# peripherals.net
KiCad netlist of a schematic drawn in Altium Designer
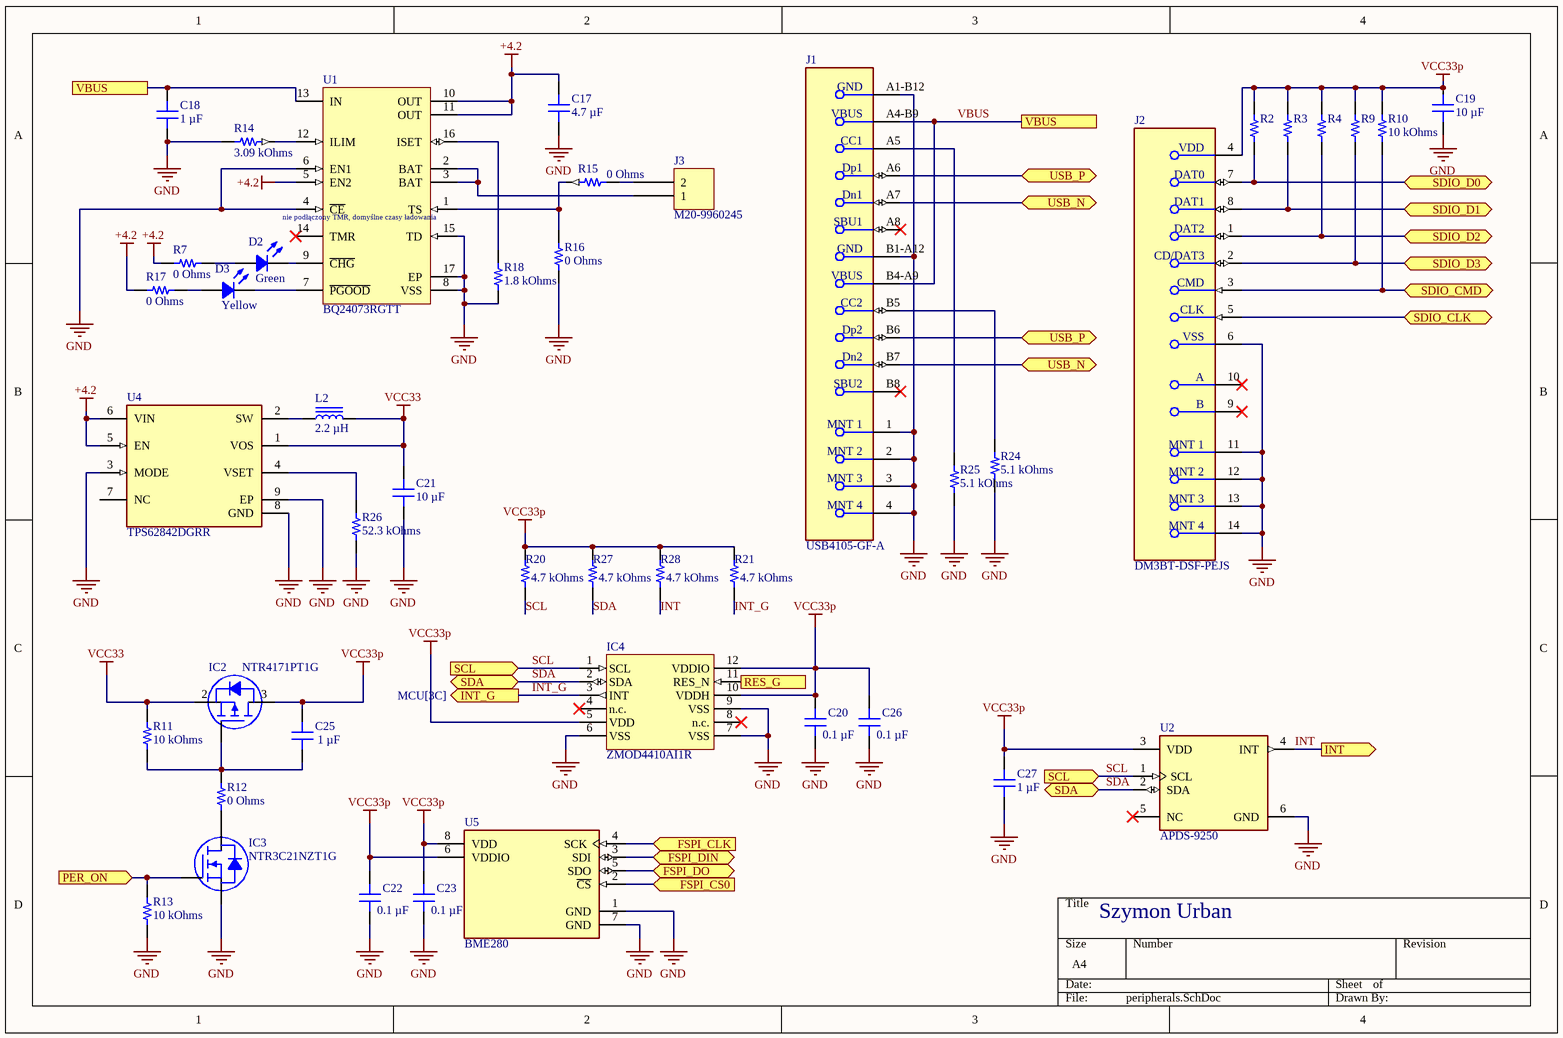
[diagram p0: peripherals.SchDoc]

(export (version "E")
  (design (tool "Eeschema 10.0.6"))
  (components
    (comp (ref "C17")
      (value "4.7 µF")
      (footprint "CAP 0603_1608")
      (description "CAP CER 4.7UF 16V X5R 0603")
      (fields
        (field (name "PART NUMBER") "GRM188R61C475KE11D")
        (field (name "MANUFACTURER") "Murata Electronics")
      )
      (libsource (lib "Celestial Altium Library - altium_library") (part "Capacitor"))
    )
    (comp (ref "C18")
      (value "1 µF")
      (footprint "CAP 0603_1608")
      (description "CAP CER 1UF 10V X7R 0603")
      (fields (field (name "PART NUMBER") "CC0603KRX7R6BB105") (field (name "MANUFACTURER") "Yageo"))
      (libsource (lib "Celestial Altium Library - altium_library") (part "Capacitor"))
    )
    (comp (ref "C19")
      (value "10 µF")
      (footprint "CAP 0603_1608")
      (description "CAP CER 10UF 10V X7T 0603")
      (fields
        (field (name "PART NUMBER") "GRM188D71A106KA73D")
        (field (name "MANUFACTURER") "Murata Electronics")
      )
      (libsource (lib "Celestial Altium Library - altium_library") (part "Capacitor"))
    )
    (comp (ref "C20")
      (value "0.1 µF")
      (footprint "CAP 0603_1608")
      (description "CAP CER 0.1UF 16V X7R 0603")
      (fields (field (name "PART NUMBER") "CS0603KRX7R7BB104") (field (name "MANUFACTURER") "Yageo"))
      (libsource (lib "Celestial Altium Library - altium_library") (part "Capacitor"))
    )
    (comp (ref "C21")
      (value "10 µF")
      (footprint "CAP 0603_1608")
      (description "CAP CER 10UF 10V X7T 0603")
      (fields
        (field (name "PART NUMBER") "GRM188D71A106KA73D")
        (field (name "MANUFACTURER") "Murata Electronics")
      )
      (libsource (lib "Celestial Altium Library - altium_library") (part "Capacitor"))
    )
    (comp (ref "C22")
      (value "0.1 µF")
      (footprint "CAP 0603_1608")
      (description "CAP CER 0.1UF 16V X7R 0603")
      (fields (field (name "PART NUMBER") "CS0603KRX7R7BB104") (field (name "MANUFACTURER") "Yageo"))
      (libsource (lib "Celestial Altium Library - altium_library") (part "Capacitor"))
    )
    (comp (ref "C23")
      (value "0.1 µF")
      (footprint "CAP 0603_1608")
      (description "CAP CER 0.1UF 16V X7R 0603")
      (fields (field (name "PART NUMBER") "CS0603KRX7R7BB104") (field (name "MANUFACTURER") "Yageo"))
      (libsource (lib "Celestial Altium Library - altium_library") (part "Capacitor"))
    )
    (comp (ref "C25")
      (value "1 µF")
      (footprint "CAP 0603_1608")
      (description "CAP CER 1UF 10V X7R 0603")
      (fields
        (field (name "PART NUMBER") "CC0603KRX7R6BB105")
        (field (name "CAPACITANCE") "1 µF")
        (field (name "MANUFACTURER") "Yageo")
      )
      (libsource (lib "Celestial Altium Library - altium_library") (part "Capacitor"))
    )
    (comp (ref "C26")
      (value "0.1 µF")
      (footprint "CAP 0603_1608")
      (description "CAP CER 0.1UF 16V X7R 0603")
      (fields (field (name "PART NUMBER") "CS0603KRX7R7BB104") (field (name "MANUFACTURER") "Yageo"))
      (libsource (lib "Celestial Altium Library - altium_library") (part "Capacitor"))
    )
    (comp (ref "C27")
      (value "1 µF")
      (footprint "CAP 0603_1608")
      (description "CAP CER 1UF 10V X7R 0603")
      (fields (field (name "PART NUMBER") "CC0603KRX7R6BB105") (field (name "MANUFACTURER") "Yageo"))
      (libsource (lib "Celestial Altium Library - altium_library") (part "Capacitor"))
    )
    (comp (ref "D2")
      (value "Green")
      (footprint "LED 0805_2012 GREEN")
      (description "LED GREEN CLEAR 0805 SMD")
      (fields (field (name "PART NUMBER") "150080VS75000") (field (name "MANUFACTURER") "Würth Elektronik"))
      (libsource (lib "Celestial Altium Library - altium_library") (part "LED"))
    )
    (comp (ref "D3")
      (value "Yellow")
      (footprint "LED 0805_2012 YELLOW")
      (description "LED YELLOW CLEAR 0805 SMD")
      (fields (field (name "PART NUMBER") "150080YS75000") (field (name "MANUFACTURER") "Würth Elektronik"))
      (libsource (lib "Celestial Altium Library - altium_library") (part "LED"))
    )
    (comp (ref "IC2")
      (value "NTR4171PT1G")
      (footprint "ON SEMI SOT-23-3")
      (description "MOSFET P-CH 30V 2.2A SOT23")
      (fields (field (name "MANUFACTURER") "ON Semiconductor"))
      (libsource (lib "Celestial Altium Library - altium_library") (part "ON SEMI MOSFET P-CH SOT-23-3"))
    )
    (comp (ref "IC3")
      (value "NTR3C21NZT1G")
      (footprint "ON SEMI SOT-23-3")
      (description "MOSFET N-CH 20V 3.6A SOT23-3")
      (fields (field (name "MANUFACTURER") "ON Semiconductor"))
      (libsource (lib "Celestial Altium Library - altium_library") (part "ON SEMI MOSFET N-CH SOT-23-3"))
    )
    (comp (ref "IC4")
      (value "ZMOD4410AI1R")
      (footprint "ZMODxxxx 12 Leads- LGG12")
      (description "TVOC IAQ INTEGRATED SENSOR")
      (libsource (lib "Altium Content Vault") (part "ZMOD4410AI1R"))
    )
    (comp (ref "J1")
      (value "USB4105-GF-A")
      (footprint "FP-USB4105-GF-A-MFG")
      (description "CONN RCPT USB2.0 TYPEC 5A")
      (fields
        (field (name "MANUFACTURER") "GCT")
        (field (name "OCTOPART") "https://octopart.com/usb4105-gf-a-gct-106627878")
      )
      (libsource (lib "Altium Content Vault") (part "e7c17a616881a82b79941196b4bec10"))
    )
    (comp (ref "J2")
      (value "DM3BT-DSF-PEJS")
      (footprint "FP-DM3BT-DSF-PEJS-MFG")
      (description "CONN MICRO SD CARD PUSH-PUSH R/A")
      (libsource (lib "Altium Content Vault") (part "93546ed2a3e5f67d674769dc1278528"))
    )
    (comp (ref "J3")
      (value "M20-9960245")
      (footprint "HARWIN M20-9960245")
      (description "CONN HEADER R/A 2POS 2.54MM")
      (fields (field (name "MANUFACTURER") "Harwin Inc."))
      (libsource (lib "Celestial Altium Library - altium_library") (part "2 Pin"))
    )
    (comp (ref "L2")
      (value "2.2 µH")
      (footprint "IND 0806_2016")
      (description "FIXED IND 2.2UH 1.8A 116MOHM SMD")
      (fields
        (field (name "PART NUMBER") "DFE201612E-2R2M=P2")
        (field (name "MANUFACTURER") "Murata Electronics")
      )
      (libsource (lib "Celestial Altium Library - altium_library") (part "Inductor"))
    )
    (comp (ref "R2")
      (value "10 kOhms")
      (footprint "RES 0603_1608")
      (description "RES SMD 10K OHM 1% 1/10W 0603")
      (fields (field (name "PART NUMBER") "RT0603FRE0710KL") (field (name "MANUFACTURER") "Yageo"))
      (libsource (lib "Celestial Altium Library - altium_library") (part "Resistor"))
    )
    (comp (ref "R3")
      (value "10 kOhms")
      (footprint "RES 0603_1608")
      (description "RES SMD 10K OHM 1% 1/10W 0603")
      (fields (field (name "PART NUMBER") "RT0603FRE0710KL") (field (name "MANUFACTURER") "Yageo"))
      (libsource (lib "Celestial Altium Library - altium_library") (part "Resistor"))
    )
    (comp (ref "R4")
      (value "10 kOhms")
      (footprint "RES 0603_1608")
      (description "RES SMD 10K OHM 1% 1/10W 0603")
      (fields (field (name "PART NUMBER") "RT0603FRE0710KL") (field (name "MANUFACTURER") "Yageo"))
      (libsource (lib "Celestial Altium Library - altium_library") (part "Resistor"))
    )
    (comp (ref "R7")
      (value "0 Ohms")
      (footprint "RES 0603_1608")
      (description "0603 26 AMP JUMPER")
      (fields (field (name "PART NUMBER") "JR0603X26E") (field (name "MANUFACTURER") "Ohmite"))
      (libsource (lib "Celestial Altium Library - altium_library") (part "Resistor"))
    )
    (comp (ref "R9")
      (value "10 kOhms")
      (footprint "RES 0603_1608")
      (description "RES SMD 10K OHM 1% 1/10W 0603")
      (fields (field (name "PART NUMBER") "RT0603FRE0710KL") (field (name "MANUFACTURER") "Yageo"))
      (libsource (lib "Celestial Altium Library - altium_library") (part "Resistor"))
    )
    (comp (ref "R10")
      (value "10 kOhms")
      (footprint "RES 0603_1608")
      (description "RES SMD 10K OHM 1% 1/10W 0603")
      (fields (field (name "PART NUMBER") "RT0603FRE0710KL") (field (name "MANUFACTURER") "Yageo"))
      (libsource (lib "Celestial Altium Library - altium_library") (part "Resistor"))
    )
    (comp (ref "R11")
      (value "10 kOhms")
      (footprint "RES 0603_1608")
      (description "RES 10K OHM 1% 1/10W 0603")
      (fields (field (name "PART NUMBER") "TNPW060310K0FHTA") (field (name "MANUFACTURER") "Vishay Dale"))
      (libsource (lib "Celestial Altium Library - altium_library") (part "Resistor"))
    )
    (comp (ref "R12")
      (value "0 Ohms")
      (footprint "RES 0603_1608")
      (description "0603 26 AMP JUMPER")
      (fields (field (name "PART NUMBER") "JR0603X26E") (field (name "MANUFACTURER") "Ohmite"))
      (libsource (lib "Celestial Altium Library - altium_library") (part "Resistor"))
    )
    (comp (ref "R13")
      (value "10 kOhms")
      (footprint "RES 0603_1608")
      (description "RES 10K OHM 1% 1/10W 0603")
      (fields (field (name "PART NUMBER") "TNPW060310K0FHTA") (field (name "MANUFACTURER") "Vishay Dale"))
      (libsource (lib "Celestial Altium Library - altium_library") (part "Resistor"))
    )
    (comp (ref "R14")
      (value "3.09 kOhms")
      (footprint "RES 0603_1608")
      (description "RES 3.09K OHM 1% 1/10W 0603")
      (fields
        (field (name "PART NUMBER") "RMCF0603FT3K09")
        (field (name "MANUFACTURER") "Stackpole Electronics Inc")
      )
      (libsource (lib "") (part "Resistor_1"))
    )
    (comp (ref "R15")
      (value "0 Ohms")
      (footprint "RES 0603_1608")
      (description "0603 26 AMP JUMPER")
      (fields (field (name "PART NUMBER") "JR0603X26E") (field (name "MANUFACTURER") "Ohmite"))
      (libsource (lib "Celestial Altium Library - altium_library") (part "Resistor"))
    )
    (comp (ref "R16")
      (value "0 Ohms")
      (footprint "RES 0603_1608")
      (description "0603 26 AMP JUMPER")
      (fields (field (name "PART NUMBER") "JR0603X26E") (field (name "MANUFACTURER") "Ohmite"))
      (libsource (lib "Celestial Altium Library - altium_library") (part "Resistor"))
    )
    (comp (ref "R17")
      (value "0 Ohms")
      (footprint "RES 0603_1608")
      (description "0603 26 AMP JUMPER")
      (fields (field (name "PART NUMBER") "JR0603X26E") (field (name "MANUFACTURER") "Ohmite"))
      (libsource (lib "Celestial Altium Library - altium_library") (part "Resistor"))
    )
    (comp (ref "R18")
      (value "1.8 kOhms")
      (footprint "RES 0603_1608")
      (description "RES 1.8K OHM 5% 1/10W 0603")
      (fields
        (field (name "PART NUMBER") "RMCF0603JG1K80")
        (field (name "MANUFACTURER") "Stackpole Electronics Inc")
      )
      (libsource (lib "Celestial Altium Library - altium_library") (part "Resistor"))
    )
    (comp (ref "R20")
      (value "4.7 kOhms")
      (footprint "RES 0603_1608")
      (description "RES 4.7K OHM 0.1% 1/10W 0603")
      (fields (field (name "PART NUMBER") "TNPW06034K70BEEN") (field (name "MANUFACTURER") "Vishay Dale"))
      (libsource (lib "Celestial Altium Library - altium_library") (part "Resistor"))
    )
    (comp (ref "R21")
      (value "4.7 kOhms")
      (footprint "RES 0603_1608")
      (description "RES 4.7K OHM 0.1% 1/10W 0603")
      (fields (field (name "PART NUMBER") "TNPW06034K70BEEN") (field (name "MANUFACTURER") "Vishay Dale"))
      (libsource (lib "Celestial Altium Library - altium_library") (part "Resistor"))
    )
    (comp (ref "R24")
      (value "5.1 kOhms")
      (footprint "RES 0603_1608")
      (description "RES SMD 5.1K OHM 0.5% 1/16W 0603")
      (fields (field (name "PART NUMBER") "RR0816P-512-D") (field (name "MANUFACTURER") "Susumu"))
      (libsource (lib "Celestial Altium Library - altium_library") (part "Resistor"))
    )
    (comp (ref "R25")
      (value "5.1 kOhms")
      (footprint "RES 0603_1608")
      (description "RES SMD 5.1K OHM 0.5% 1/16W 0603")
      (fields (field (name "PART NUMBER") "RR0816P-512-D") (field (name "MANUFACTURER") "Susumu"))
      (libsource (lib "Celestial Altium Library - altium_library") (part "Resistor"))
    )
    (comp (ref "R26")
      (value "52.3 kOhms")
      (footprint "RES 0603_1608")
      (description "RES 52.3K OHM 1% 1/10W 0603")
      (fields (field (name "PART NUMBER") "RC0603FR-1052K3L") (field (name "MANUFACTURER") "Yageo"))
      (libsource (lib "Celestial Altium Library - altium_library") (part "Resistor"))
    )
    (comp (ref "R27")
      (value "4.7 kOhms")
      (footprint "RES 0603_1608")
      (description "RES 4.7K OHM 0.1% 1/10W 0603")
      (fields (field (name "PART NUMBER") "TNPW06034K70BEEN") (field (name "MANUFACTURER") "Vishay Dale"))
      (libsource (lib "Celestial Altium Library - altium_library") (part "Resistor"))
    )
    (comp (ref "R28")
      (value "4.7 kOhms")
      (footprint "RES 0603_1608")
      (description "RES 4.7K OHM 0.1% 1/10W 0603")
      (fields (field (name "PART NUMBER") "TNPW06034K70BEEN") (field (name "MANUFACTURER") "Vishay Dale"))
      (libsource (lib "Celestial Altium Library - altium_library") (part "Resistor"))
    )
    (comp (ref "U1")
      (value "BQ24073RGTT")
      (footprint "RGT0016C_V")
      (fields (field (name "MANUFACTURER") "Texas Instruments"))
      (libsource (lib "Altium Content Vault") (part "TI-BQ24073RGT16-1700X1700TP"))
    )
    (comp (ref "U2")
      (value "APDS-9250")
      (footprint "FP-APDS-9250-MFG")
      (description "SENSOR OPT 550NM AMBIENT 6SMD")
      (fields
        (field (name "MANUFACTURER") "Broadcom")
        (field (name "OCTOPART") "https://octopart.com/apds-9250-broadcom-71127178")
      )
      (libsource (lib "Altium Content Vault") (part "6c7eaf7f932280e5aebfe08785c1cfa"))
    )
    (comp (ref "U4")
      (value "TPS62842DGRR")
      (footprint "FP-DGR0008A-MFG")
      (description "STEP DOWN CONVERTER")
      (libsource (lib "Altium Content Vault") (part "8ee1c446ca40a49d0fd1cd25675394a"))
    )
    (comp (ref "U5")
      (value "BME280")
      (footprint "FP-BME280-MFG")
      (description "SENSOR PRESSURE HUMIDITY TEMP")
      (libsource (lib "Altium Content Vault") (part "d58e2f6669bc67e6a2bc6a28610ca79"))
    )
  )
  (nets
    (net (code "1") (name "+4.2") (class "Default")
      (node (ref "C17") (pin "2") (pinfunction "2_2") (pintype "passive"))
      (node (ref "R17") (pin "2") (pinfunction "2_2") (pintype "passive"))
      (node (ref "R7") (pin "2") (pinfunction "2_2") (pintype "passive"))
      (node (ref "U1") (pin "10") (pinfunction "OUT_10") (pintype "power_in"))
      (node (ref "U1") (pin "11") (pinfunction "OUT_11") (pintype "power_in"))
      (node (ref "U1") (pin "5") (pinfunction "EN2_5") (pintype "input"))
      (node (ref "U4") (pin "5") (pinfunction "EN_5") (pintype "input"))
      (node (ref "U4") (pin "6") (pinfunction "VIN_6") (pintype "power_in"))
    )
    (net (code "2") (name "/FSPI_CLK") (class "Default")
      (node (ref "U5") (pin "4") (pinfunction "SCK_4") (pintype "input"))
    )
    (net (code "3") (name "/FSPI_CS0") (class "Default")
      (node (ref "U5") (pin "2") (pinfunction "~{CS}_2") (pintype "input"))
    )
    (net (code "4") (name "/FSPI_DIN") (class "Default")
      (node (ref "U5") (pin "3") (pinfunction "SDI_3") (pintype "bidirectional"))
    )
    (net (code "5") (name "/FSPI_DO") (class "Default")
      (node (ref "U5") (pin "5") (pinfunction "SDO_5") (pintype "bidirectional"))
    )
    (net (code "6") (name "/INT") (class "Default")
      (node (ref "R28") (pin "2") (pinfunction "2_2") (pintype "passive"))
      (node (ref "U2") (pin "4") (pinfunction "INT_4") (pintype "output"))
    )
    (net (code "7") (name "/INT_G") (class "Default")
      (node (ref "IC4") (pin "3") (pinfunction "INT_3") (pintype "output"))
      (node (ref "R21") (pin "2") (pinfunction "2_2") (pintype "passive"))
    )
    (net (code "8") (name "/PER_ON") (class "Default")
      (node (ref "IC3") (pin "1") (pinfunction "G_1") (pintype "passive"))
      (node (ref "R13") (pin "2") (pinfunction "2_2") (pintype "passive"))
    )
    (net (code "9") (name "/RES_G") (class "Default")
      (node (ref "IC4") (pin "11") (pinfunction "RES_N_11") (pintype "input"))
    )
    (net (code "10") (name "/SCL") (class "Default")
      (node (ref "IC4") (pin "1") (pinfunction "SCL_1") (pintype "input"))
      (node (ref "R20") (pin "2") (pinfunction "2_2") (pintype "passive"))
      (node (ref "U2") (pin "1") (pinfunction "SCL_1") (pintype "input"))
    )
    (net (code "11") (name "/SDA") (class "Default")
      (node (ref "IC4") (pin "2") (pinfunction "SDA_2") (pintype "bidirectional"))
      (node (ref "R27") (pin "2") (pinfunction "2_2") (pintype "passive"))
      (node (ref "U2") (pin "2") (pinfunction "SDA_2") (pintype "bidirectional"))
    )
    (net (code "12") (name "/SDIO_CLK") (class "Default")
      (node (ref "J2") (pin "5") (pinfunction "CLK_5") (pintype "input"))
    )
    (net (code "13") (name "/SDIO_CMD") (class "Default")
      (node (ref "J2") (pin "3") (pinfunction "CMD_3") (pintype "input"))
      (node (ref "R10") (pin "1") (pinfunction "1_1") (pintype "passive"))
    )
    (net (code "14") (name "/SDIO_D0") (class "Default")
      (node (ref "J2") (pin "7") (pinfunction "DAT0_7") (pintype "bidirectional"))
      (node (ref "R2") (pin "1") (pinfunction "1_1") (pintype "passive"))
    )
    (net (code "15") (name "/SDIO_D1") (class "Default")
      (node (ref "J2") (pin "8") (pinfunction "DAT1_8") (pintype "bidirectional"))
      (node (ref "R3") (pin "1") (pinfunction "1_1") (pintype "passive"))
    )
    (net (code "16") (name "/SDIO_D2") (class "Default")
      (node (ref "J2") (pin "1") (pinfunction "DAT2_1") (pintype "bidirectional"))
      (node (ref "R4") (pin "1") (pinfunction "1_1") (pintype "passive"))
    )
    (net (code "17") (name "/SDIO_D3") (class "Default")
      (node (ref "J2") (pin "2") (pinfunction "CD/DAT3_2") (pintype "bidirectional"))
      (node (ref "R9") (pin "1") (pinfunction "1_1") (pintype "passive"))
    )
    (net (code "18") (name "/USB_N") (class "Default")
      (node (ref "J1") (pin "A7") (pinfunction "Dn1_A7") (pintype "bidirectional"))
      (node (ref "J1") (pin "B7") (pinfunction "Dn2_B7") (pintype "bidirectional"))
    )
    (net (code "19") (name "/USB_P") (class "Default")
      (node (ref "J1") (pin "A6") (pinfunction "Dp1_A6") (pintype "bidirectional"))
      (node (ref "J1") (pin "B6") (pinfunction "Dp2_B6") (pintype "bidirectional"))
    )
    (net (code "20") (name "/VBUS") (class "Default")
      (node (ref "C18") (pin "2") (pinfunction "2_2") (pintype "passive"))
      (node (ref "J1") (pin "A4-B9") (pinfunction "VBUS_A4-B9") (pintype "power_in"))
      (node (ref "J1") (pin "B4-A9") (pinfunction "VBUS_B4-A9") (pintype "power_in"))
      (node (ref "U1") (pin "13") (pinfunction "IN_13") (pintype "power_in"))
    )
    (net (code "21") (name "GND") (class "Default")
      (node (ref "C17") (pin "1") (pinfunction "1_1") (pintype "passive"))
      (node (ref "C18") (pin "1") (pinfunction "1_1") (pintype "passive"))
      (node (ref "C19") (pin "2") (pinfunction "2_2") (pintype "passive"))
      (node (ref "C20") (pin "1") (pinfunction "1_1") (pintype "passive"))
      (node (ref "C21") (pin "2") (pinfunction "2_2") (pintype "passive"))
      (node (ref "C22") (pin "1") (pinfunction "1_1") (pintype "passive"))
      (node (ref "C23") (pin "1") (pinfunction "1_1") (pintype "passive"))
      (node (ref "C26") (pin "1") (pinfunction "1_1") (pintype "passive"))
      (node (ref "C27") (pin "1") (pinfunction "1_1") (pintype "passive"))
      (node (ref "IC3") (pin "2") (pinfunction "S_2") (pintype "passive"))
      (node (ref "IC4") (pin "6") (pinfunction "VSS_6") (pintype "power_in"))
      (node (ref "IC4") (pin "7") (pinfunction "VSS_7") (pintype "power_in"))
      (node (ref "IC4") (pin "9") (pinfunction "VSS_9") (pintype "power_in"))
      (node (ref "J1") (pin "1") (pinfunction "MNT_1_1") (pintype "power_in"))
      (node (ref "J1") (pin "2") (pinfunction "MNT_2_2") (pintype "power_in"))
      (node (ref "J1") (pin "3") (pinfunction "MNT_3_3") (pintype "power_in"))
      (node (ref "J1") (pin "4") (pinfunction "MNT_4_4") (pintype "power_in"))
      (node (ref "J1") (pin "A1-B12") (pinfunction "GND_A1-B12") (pintype "power_in"))
      (node (ref "J1") (pin "B1-A12") (pinfunction "GND_B1-A12") (pintype "power_in"))
      (node (ref "J2") (pin "11") (pinfunction "MNT_1_11") (pintype "passive"))
      (node (ref "J2") (pin "12") (pinfunction "MNT_2_12") (pintype "passive"))
      (node (ref "J2") (pin "13") (pinfunction "MNT_3_13") (pintype "passive"))
      (node (ref "J2") (pin "14") (pinfunction "MNT_4_14") (pintype "passive"))
      (node (ref "J2") (pin "6") (pinfunction "VSS_6") (pintype "power_in"))
      (node (ref "R13") (pin "1") (pinfunction "1_1") (pintype "passive"))
      (node (ref "R14") (pin "1") (pinfunction "1_1") (pintype "passive"))
      (node (ref "R16") (pin "1") (pinfunction "1_1") (pintype "passive"))
      (node (ref "R18") (pin "1") (pinfunction "1_1") (pintype "passive"))
      (node (ref "R24") (pin "1") (pinfunction "1_1") (pintype "passive"))
      (node (ref "R25") (pin "1") (pinfunction "1_1") (pintype "passive"))
      (node (ref "R26") (pin "1") (pinfunction "1_1") (pintype "passive"))
      (node (ref "U1") (pin "15") (pinfunction "TD_15") (pintype "input"))
      (node (ref "U1") (pin "17") (pinfunction "EP_17") (pintype "power_in"))
      (node (ref "U1") (pin "4") (pinfunction "~{CE}_4") (pintype "input"))
      (node (ref "U1") (pin "6") (pinfunction "EN1_6") (pintype "input"))
      (node (ref "U1") (pin "8") (pinfunction "VSS_8") (pintype "power_in"))
      (node (ref "U2") (pin "6") (pinfunction "GND_6") (pintype "power_in"))
      (node (ref "U4") (pin "3") (pinfunction "MODE_3") (pintype "input"))
      (node (ref "U4") (pin "8") (pinfunction "GND_8") (pintype "power_in"))
      (node (ref "U4") (pin "9") (pinfunction "EP_9") (pintype "passive"))
      (node (ref "U5") (pin "1") (pinfunction "GND_1") (pintype "power_in"))
      (node (ref "U5") (pin "7") (pinfunction "GND_7") (pintype "power_in"))
    )
    (net (code "22") (name "Net-(D2-Pad1)") (class "Default")
      (node (ref "D2") (pin "1") (pinfunction "1_1") (pintype "passive"))
      (node (ref "R7") (pin "1") (pinfunction "1_1") (pintype "passive"))
    )
    (net (code "23") (name "Net-(D3-Pad1)") (class "Default")
      (node (ref "D3") (pin "1") (pinfunction "1_1") (pintype "passive"))
      (node (ref "R17") (pin "1") (pinfunction "1_1") (pintype "passive"))
    )
    (net (code "24") (name "Net-(IC2-G)") (class "Default")
      (node (ref "C25") (pin "1") (pinfunction "1_1") (pintype "passive"))
      (node (ref "IC2") (pin "1") (pinfunction "G_1") (pintype "passive"))
      (node (ref "R11") (pin "1") (pinfunction "1_1") (pintype "passive"))
      (node (ref "R12") (pin "2") (pinfunction "2_2") (pintype "passive"))
    )
    (net (code "25") (name "Net-(IC3-D)") (class "Default")
      (node (ref "IC3") (pin "3") (pinfunction "D_3") (pintype "passive"))
      (node (ref "R12") (pin "1") (pinfunction "1_1") (pintype "passive"))
    )
    (net (code "26") (name "Net-(J1-CC1)") (class "Default")
      (node (ref "J1") (pin "A5") (pinfunction "CC1_A5") (pintype "power_in"))
      (node (ref "R25") (pin "2") (pinfunction "2_2") (pintype "passive"))
    )
    (net (code "27") (name "Net-(J1-CC2)") (class "Default")
      (node (ref "J1") (pin "B5") (pinfunction "CC2_B5") (pintype "bidirectional"))
      (node (ref "R24") (pin "2") (pinfunction "2_2") (pintype "passive"))
    )
    (net (code "28") (name "Net-(J3-Pad1)") (class "Default")
      (node (ref "J3") (pin "1") (pinfunction "1_1") (pintype "passive"))
      (node (ref "U1") (pin "2") (pinfunction "BAT_2") (pintype "power_in"))
      (node (ref "U1") (pin "3") (pinfunction "BAT_3") (pintype "power_in"))
    )
    (net (code "29") (name "Net-(J3-Pad2)") (class "Default")
      (node (ref "J3") (pin "2") (pinfunction "2_2") (pintype "passive"))
      (node (ref "R15") (pin "2") (pinfunction "2_2") (pintype "passive"))
    )
    (net (code "30") (name "Net-(U1-ILIM)") (class "Default")
      (node (ref "R14") (pin "2") (pinfunction "2_2") (pintype "output"))
      (node (ref "U1") (pin "12") (pinfunction "ILIM_12") (pintype "input"))
    )
    (net (code "31") (name "Net-(U1-ISET)") (class "Default")
      (node (ref "R18") (pin "2") (pinfunction "2_2") (pintype "passive"))
      (node (ref "U1") (pin "16") (pinfunction "ISET_16") (pintype "bidirectional"))
    )
    (net (code "32") (name "Net-(U1-TS)") (class "Default")
      (node (ref "R15") (pin "1") (pinfunction "1_1") (pintype "passive"))
      (node (ref "R16") (pin "2") (pinfunction "2_2") (pintype "passive"))
      (node (ref "U1") (pin "1") (pinfunction "TS_1") (pintype "input"))
    )
    (net (code "33") (name "Net-(U1-~{CHG})") (class "Default")
      (node (ref "D2") (pin "2") (pinfunction "2_2") (pintype "passive"))
      (node (ref "U1") (pin "9") (pinfunction "~{CHG}_9") (pintype "tri_state"))
    )
    (net (code "34") (name "Net-(U1-~{PGOOD})") (class "Default")
      (node (ref "D3") (pin "2") (pinfunction "2_2") (pintype "passive"))
      (node (ref "U1") (pin "7") (pinfunction "~{PGOOD}_7") (pintype "tri_state"))
    )
    (net (code "35") (name "Net-(U4-SW)") (class "Default")
      (node (ref "L2") (pin "1") (pinfunction "1_1") (pintype "passive"))
      (node (ref "U4") (pin "2") (pinfunction "SW_2") (pintype "passive"))
    )
    (net (code "36") (name "Net-(U4-VSET)") (class "Default")
      (node (ref "R26") (pin "2") (pinfunction "2_2") (pintype "passive"))
      (node (ref "U4") (pin "4") (pinfunction "VSET_4") (pintype "passive"))
    )
    (net (code "37") (name "VCC33") (class "Default")
      (node (ref "C21") (pin "1") (pinfunction "1_1") (pintype "passive"))
      (node (ref "IC2") (pin "2") (pinfunction "S_2") (pintype "passive"))
      (node (ref "L2") (pin "2") (pinfunction "2_2") (pintype "passive"))
      (node (ref "R11") (pin "2") (pinfunction "2_2") (pintype "passive"))
      (node (ref "U4") (pin "1") (pinfunction "VOS_1") (pintype "power_in"))
    )
    (net (code "38") (name "VCC33p") (class "Default")
      (node (ref "C19") (pin "1") (pinfunction "1_1") (pintype "passive"))
      (node (ref "C20") (pin "2") (pinfunction "2_2") (pintype "passive"))
      (node (ref "C22") (pin "2") (pinfunction "2_2") (pintype "passive"))
      (node (ref "C23") (pin "2") (pinfunction "2_2") (pintype "passive"))
      (node (ref "C25") (pin "2") (pinfunction "2_2") (pintype "passive"))
      (node (ref "C26") (pin "2") (pinfunction "2_2") (pintype "passive"))
      (node (ref "C27") (pin "2") (pinfunction "2_2") (pintype "passive"))
      (node (ref "IC2") (pin "3") (pinfunction "D_3") (pintype "passive"))
      (node (ref "IC4") (pin "10") (pinfunction "VDDH_10") (pintype "power_in"))
      (node (ref "IC4") (pin "12") (pinfunction "VDDIO_12") (pintype "power_in"))
      (node (ref "IC4") (pin "5") (pinfunction "VDD_5") (pintype "power_in"))
      (node (ref "J2") (pin "4") (pinfunction "VDD_4") (pintype "power_in"))
      (node (ref "R10") (pin "2") (pinfunction "2_2") (pintype "passive"))
      (node (ref "R2") (pin "2") (pinfunction "2_2") (pintype "passive"))
      (node (ref "R20") (pin "1") (pinfunction "1_1") (pintype "passive"))
      (node (ref "R21") (pin "1") (pinfunction "1_1") (pintype "passive"))
      (node (ref "R27") (pin "1") (pinfunction "1_1") (pintype "passive"))
      (node (ref "R28") (pin "1") (pinfunction "1_1") (pintype "passive"))
      (node (ref "R3") (pin "2") (pinfunction "2_2") (pintype "passive"))
      (node (ref "R4") (pin "2") (pinfunction "2_2") (pintype "passive"))
      (node (ref "R9") (pin "2") (pinfunction "2_2") (pintype "passive"))
      (node (ref "U2") (pin "3") (pinfunction "VDD_3") (pintype "power_in"))
      (node (ref "U5") (pin "6") (pinfunction "VDDIO_6") (pintype "power_in"))
      (node (ref "U5") (pin "8") (pinfunction "VDD_8") (pintype "power_in"))
    )
    (net (code "39") (name "unconnected-(IC4-n.c.-Pad4)") (class "Default")
      (node (ref "IC4") (pin "4") (pinfunction "n.c._4") (pintype "passive+no_connect"))
    )
    (net (code "40") (name "unconnected-(IC4-n.c.-Pad8)") (class "Default")
      (node (ref "IC4") (pin "8") (pinfunction "n.c._8") (pintype "passive+no_connect"))
    )
    (net (code "41") (name "unconnected-(J1-SBU1-PadA8)") (class "Default")
      (node (ref "J1") (pin "A8") (pinfunction "SBU1_A8") (pintype "bidirectional+no_connect"))
    )
    (net (code "42") (name "unconnected-(J1-SBU2-PadB8)") (class "Default")
      (node (ref "J1") (pin "B8") (pinfunction "SBU2_B8") (pintype "power_in+no_connect"))
    )
    (net (code "43") (name "unconnected-(J2-A-Pad10)") (class "Default")
      (node (ref "J2") (pin "10") (pinfunction "A_10") (pintype "passive+no_connect"))
    )
    (net (code "44") (name "unconnected-(J2-B-Pad9)") (class "Default")
      (node (ref "J2") (pin "9") (pinfunction "B_9") (pintype "passive+no_connect"))
    )
    (net (code "45") (name "unconnected-(U1-TMR-Pad14)") (class "Default")
      (node (ref "U1") (pin "14") (pinfunction "TMR_14") (pintype "passive+no_connect"))
    )
    (net (code "46") (name "unconnected-(U2-NC-Pad5)") (class "Default")
      (node (ref "U2") (pin "5") (pinfunction "NC_5") (pintype "passive+no_connect"))
    )
    (net (code "47") (name "unconnected-(U4-NC-Pad7)") (class "Default")
      (node (ref "U4") (pin "7") (pinfunction "NC_7") (pintype "passive"))
    )
  )
)
